# Digit_2.net
KiCad netlist of a schematic drawn in Altium Designer
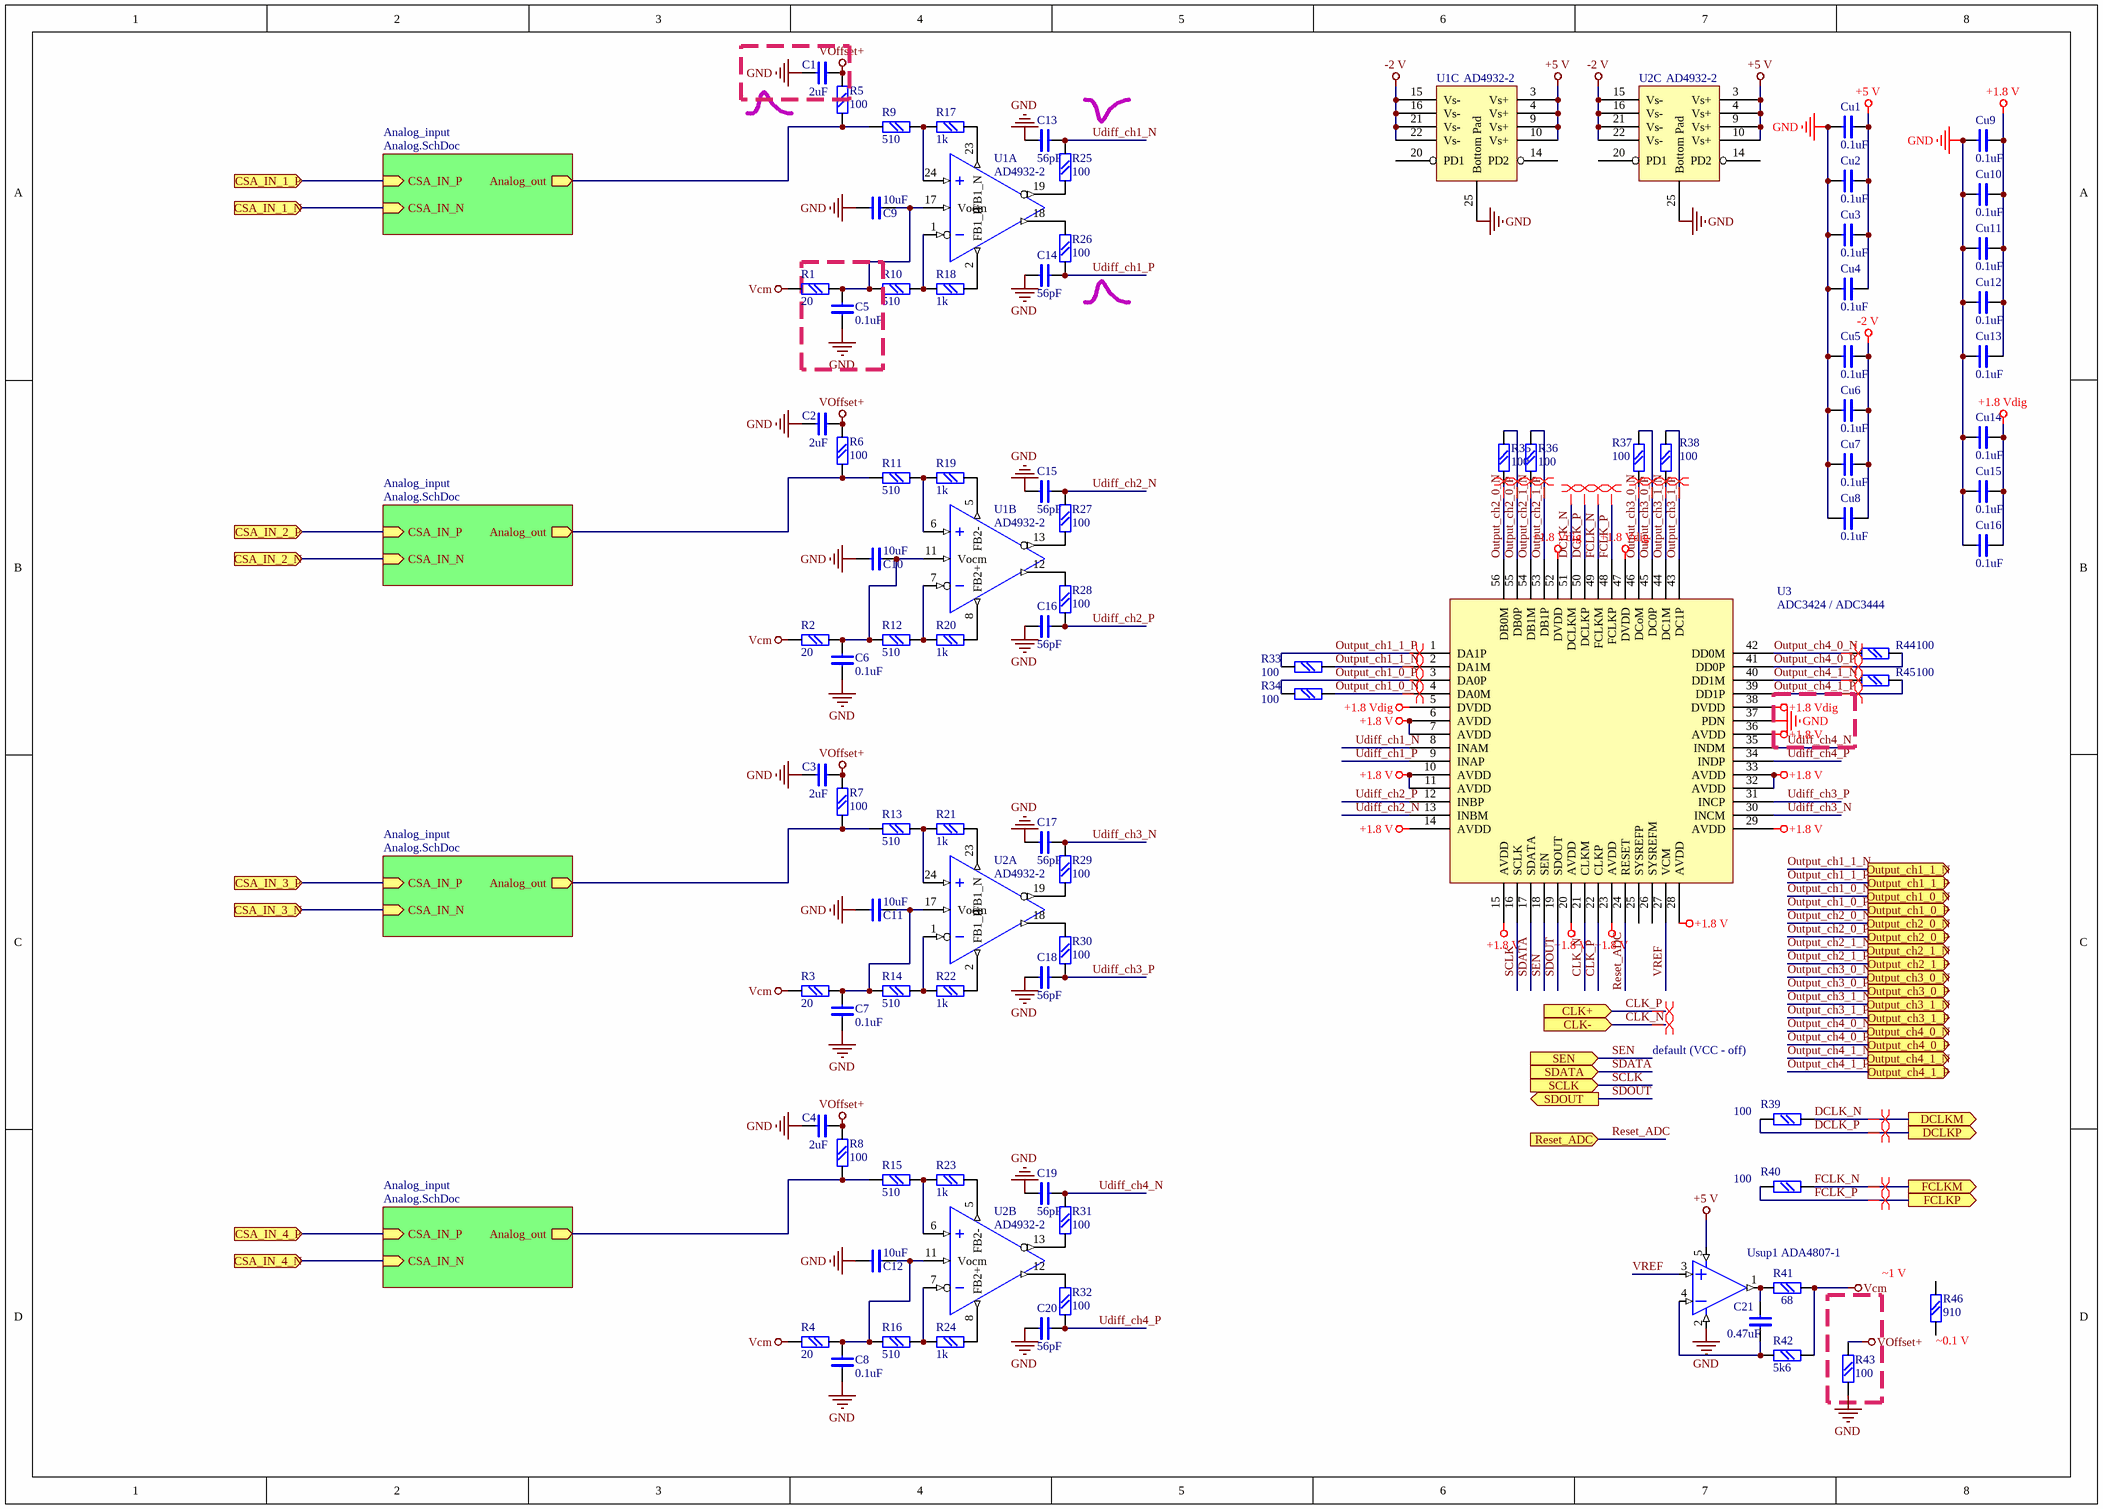
[diagram p0: Digit_2.SchDoc]

(export (version "E")
  (design (tool "Eeschema 10.0.6"))
  (components
    (comp (ref "C1") (value "2uF") (footprint "chip0603") (libsource (lib "vDevice") (part "C")))
    (comp (ref "C2") (value "2uF") (footprint "chip0603") (libsource (lib "vDevice") (part "C")))
    (comp (ref "C3") (value "2uF") (footprint "chip0603") (libsource (lib "vDevice") (part "C")))
    (comp (ref "C4") (value "2uF") (footprint "chip0603") (libsource (lib "vDevice") (part "C")))
    (comp (ref "C5") (value "0.1uF") (footprint "chip0603") (libsource (lib "vDevice") (part "C")))
    (comp (ref "C6") (value "0.1uF") (footprint "chip0603") (libsource (lib "vDevice") (part "C")))
    (comp (ref "C7") (value "0.1uF") (footprint "chip0603") (libsource (lib "vDevice") (part "C")))
    (comp (ref "C8") (value "0.1uF") (footprint "chip0603") (libsource (lib "vDevice") (part "C")))
    (comp (ref "C9") (value "10uF") (footprint "chip0603") (libsource (lib "vDevice") (part "C")))
    (comp (ref "C10") (value "10uF") (footprint "chip0603") (libsource (lib "vDevice") (part "C")))
    (comp (ref "C11") (value "10uF") (footprint "chip0603") (libsource (lib "vDevice") (part "C")))
    (comp (ref "C12") (value "10uF") (footprint "chip0603") (libsource (lib "vDevice") (part "C")))
    (comp (ref "C13") (value "56pF") (footprint "chip0603") (libsource (lib "vDevice") (part "C")))
    (comp (ref "C14") (value "56pF") (footprint "chip0603") (libsource (lib "vDevice") (part "C")))
    (comp (ref "C15") (value "56pF") (footprint "chip0603") (libsource (lib "vDevice") (part "C")))
    (comp (ref "C16") (value "56pF") (footprint "chip0603") (libsource (lib "vDevice") (part "C")))
    (comp (ref "C17") (value "56pF") (footprint "chip0603") (libsource (lib "vDevice") (part "C")))
    (comp (ref "C18") (value "56pF") (footprint "chip0603") (libsource (lib "vDevice") (part "C")))
    (comp (ref "C19") (value "56pF") (footprint "chip0603") (libsource (lib "vDevice") (part "C")))
    (comp (ref "C20") (value "56pF") (footprint "chip0603") (libsource (lib "vDevice") (part "C")))
    (comp (ref "C21") (value "0.47uF") (footprint "chip0603") (libsource (lib "*") (part "C")))
    (comp (ref "Cu1") (value "0.1uF") (footprint "chip0603") (libsource (lib "*") (part "C")))
    (comp (ref "Cu2") (value "0.1uF") (footprint "chip0603") (libsource (lib "*") (part "C")))
    (comp (ref "Cu3") (value "0.1uF") (footprint "chip0603") (libsource (lib "*") (part "C")))
    (comp (ref "Cu4") (value "0.1uF") (footprint "chip0603") (libsource (lib "*") (part "C")))
    (comp (ref "Cu5") (value "0.1uF") (footprint "chip0603") (libsource (lib "*") (part "C")))
    (comp (ref "Cu6") (value "0.1uF") (footprint "chip0603") (libsource (lib "*") (part "C")))
    (comp (ref "Cu7") (value "0.1uF") (footprint "chip0603") (libsource (lib "*") (part "C")))
    (comp (ref "Cu8") (value "0.1uF") (footprint "chip0603") (libsource (lib "*") (part "C")))
    (comp (ref "Cu9") (value "0.1uF") (footprint "chip0603") (libsource (lib "*") (part "C")))
    (comp (ref "Cu10") (value "0.1uF") (footprint "chip0603") (libsource (lib "*") (part "C")))
    (comp (ref "Cu11") (value "0.1uF") (footprint "chip0603") (libsource (lib "*") (part "C")))
    (comp (ref "Cu12") (value "0.1uF") (footprint "chip0603") (libsource (lib "*") (part "C")))
    (comp (ref "Cu13") (value "0.1uF") (footprint "chip0603") (libsource (lib "*") (part "C")))
    (comp (ref "Cu14") (value "0.1uF") (footprint "chip0603") (libsource (lib "*") (part "C")))
    (comp (ref "Cu15") (value "0.1uF") (footprint "chip0603") (libsource (lib "*") (part "C")))
    (comp (ref "Cu16") (value "0.1uF") (footprint "chip0603") (libsource (lib "*") (part "C")))
    (comp (ref "R1") (value "20") (footprint "chip0603") (libsource (lib "vDevice") (part "R")))
    (comp (ref "R2") (value "20") (footprint "chip0603") (libsource (lib "vDevice") (part "R")))
    (comp (ref "R3") (value "20") (footprint "chip0603") (libsource (lib "vDevice") (part "R")))
    (comp (ref "R4") (value "20") (footprint "chip0603") (libsource (lib "vDevice") (part "R")))
    (comp (ref "R5") (value "100") (footprint "chip0603") (libsource (lib "vDevice") (part "R")))
    (comp (ref "R6") (value "100") (footprint "chip0603") (libsource (lib "vDevice") (part "R")))
    (comp (ref "R7") (value "100") (footprint "chip0603") (libsource (lib "vDevice") (part "R")))
    (comp (ref "R8") (value "100") (footprint "chip0603") (libsource (lib "vDevice") (part "R")))
    (comp (ref "R9") (value "510") (footprint "chip0603") (libsource (lib "vDevice") (part "R")))
    (comp (ref "R10") (value "510") (footprint "chip0603") (libsource (lib "vDevice") (part "R")))
    (comp (ref "R11") (value "510") (footprint "chip0603") (libsource (lib "vDevice") (part "R")))
    (comp (ref "R12") (value "510") (footprint "chip0603") (libsource (lib "vDevice") (part "R")))
    (comp (ref "R13") (value "510") (footprint "chip0603") (libsource (lib "vDevice") (part "R")))
    (comp (ref "R14") (value "510") (footprint "chip0603") (libsource (lib "vDevice") (part "R")))
    (comp (ref "R15") (value "510") (footprint "chip0603") (libsource (lib "vDevice") (part "R")))
    (comp (ref "R16") (value "510") (footprint "chip0603") (libsource (lib "vDevice") (part "R")))
    (comp (ref "R17") (value "1k") (footprint "chip0603") (libsource (lib "vDevice") (part "R")))
    (comp (ref "R18") (value "1k") (footprint "chip0603") (libsource (lib "vDevice") (part "R")))
    (comp (ref "R19") (value "1k") (footprint "chip0603") (libsource (lib "vDevice") (part "R")))
    (comp (ref "R20") (value "1k") (footprint "chip0603") (libsource (lib "vDevice") (part "R")))
    (comp (ref "R21") (value "1k") (footprint "chip0603") (libsource (lib "vDevice") (part "R")))
    (comp (ref "R22") (value "1k") (footprint "chip0603") (libsource (lib "vDevice") (part "R")))
    (comp (ref "R23") (value "1k") (footprint "chip0603") (libsource (lib "vDevice") (part "R")))
    (comp (ref "R24") (value "1k") (footprint "chip0603") (libsource (lib "vDevice") (part "R")))
    (comp (ref "R25") (value "100") (footprint "chip0603") (libsource (lib "vDevice") (part "R")))
    (comp (ref "R26") (value "100") (footprint "chip0603") (libsource (lib "vDevice") (part "R")))
    (comp (ref "R27") (value "100") (footprint "chip0603") (libsource (lib "vDevice") (part "R")))
    (comp (ref "R28") (value "100") (footprint "chip0603") (libsource (lib "vDevice") (part "R")))
    (comp (ref "R29") (value "100") (footprint "chip0603") (libsource (lib "vDevice") (part "R")))
    (comp (ref "R30") (value "100") (footprint "chip0603") (libsource (lib "vDevice") (part "R")))
    (comp (ref "R31") (value "100") (footprint "chip0603") (libsource (lib "vDevice") (part "R")))
    (comp (ref "R32") (value "100") (footprint "chip0603") (libsource (lib "vDevice") (part "R")))
    (comp (ref "R33") (value "100") (footprint "0402") (libsource (lib "vDevice") (part "R")))
    (comp (ref "R34") (value "100") (footprint "0402") (libsource (lib "vDevice") (part "R")))
    (comp (ref "R35") (value "100") (footprint "0402") (libsource (lib "vDevice") (part "R")))
    (comp (ref "R36") (value "100") (footprint "0402") (libsource (lib "vDevice") (part "R")))
    (comp (ref "R37") (value "100") (footprint "0402") (libsource (lib "vDevice") (part "R")))
    (comp (ref "R38") (value "100") (footprint "0402") (libsource (lib "vDevice") (part "R")))
    (comp (ref "R39") (value "100") (footprint "0402") (libsource (lib "vDevice") (part "R")))
    (comp (ref "R40") (value "100") (footprint "0402") (libsource (lib "vDevice") (part "R")))
    (comp (ref "R41") (value "68") (footprint "chip0603") (libsource (lib "vDevice") (part "R")))
    (comp (ref "R42") (value "5k6") (footprint "chip0603") (libsource (lib "vDevice") (part "R")))
    (comp (ref "R43") (value "100") (footprint "chip0603") (libsource (lib "vDevice") (part "R")))
    (comp (ref "R44") (value "100") (footprint "0402") (libsource (lib "vDevice") (part "R")))
    (comp (ref "R45") (value "100") (footprint "0402") (libsource (lib "vDevice") (part "R")))
    (comp (ref "R46") (value "910") (footprint "chip0603") (libsource (lib "vDevice") (part "R")))
    (comp (ref "U1")
      (value "AD4932-2")
      (footprint "CP-24-13")
      (libsource (lib "Backup of Mylib") (part "AD4932-2"))
    )
    (comp (ref "U2") (value "AD4932-2") (footprint "CP-24-13") (libsource (lib "") (part "AD4932-2_1")))
    (comp (ref "U3")
      (value "ADC3424 / ADC3444")
      (footprint "PQFN-56")
      (libsource (lib "Backup of Mylib") (part "ADC3424"))
    )
    (comp (ref "Usup1")
      (value "ADA4807-1")
      (footprint "SOT23-5")
      (libsource (lib "vAnalog") (part "AD8005ART"))
    )
  )
  (nets
    (net (code "1") (name "+1.8 V") (class "Default")
      (node (ref "Cu10") (pin "2") (pinfunction "2_2") (pintype "passive"))
      (node (ref "Cu11") (pin "2") (pinfunction "2_2") (pintype "passive"))
      (node (ref "Cu12") (pin "2") (pinfunction "2_2") (pintype "passive"))
      (node (ref "Cu13") (pin "2") (pinfunction "2_2") (pintype "passive"))
      (node (ref "Cu9") (pin "2") (pinfunction "2_2") (pintype "passive"))
      (node (ref "U3") (pin "10") (pinfunction "AVDD_10") (pintype "passive"))
      (node (ref "U3") (pin "11") (pinfunction "AVDD_11") (pintype "passive"))
      (node (ref "U3") (pin "14") (pinfunction "AVDD_14") (pintype "passive"))
      (node (ref "U3") (pin "15") (pinfunction "AVDD_15") (pintype "passive"))
      (node (ref "U3") (pin "20") (pinfunction "AVDD_20") (pintype "passive"))
      (node (ref "U3") (pin "23") (pinfunction "AVDD_23") (pintype "passive"))
      (node (ref "U3") (pin "28") (pinfunction "AVDD_28") (pintype "passive"))
      (node (ref "U3") (pin "29") (pinfunction "AVDD_29") (pintype "passive"))
      (node (ref "U3") (pin "32") (pinfunction "AVDD_32") (pintype "passive"))
      (node (ref "U3") (pin "33") (pinfunction "AVDD_33") (pintype "passive"))
      (node (ref "U3") (pin "36") (pinfunction "AVDD_36") (pintype "passive"))
      (node (ref "U3") (pin "6") (pinfunction "AVDD_6") (pintype "passive"))
      (node (ref "U3") (pin "7") (pinfunction "AVDD_7") (pintype "passive"))
    )
    (net (code "2") (name "+1.8 Vdig") (class "Default")
      (node (ref "Cu14") (pin "2") (pinfunction "2_2") (pintype "passive"))
      (node (ref "Cu15") (pin "2") (pinfunction "2_2") (pintype "passive"))
      (node (ref "Cu16") (pin "2") (pinfunction "2_2") (pintype "passive"))
      (node (ref "U3") (pin "38") (pinfunction "DVDD_38") (pintype "passive"))
      (node (ref "U3") (pin "47") (pinfunction "DVDD_47") (pintype "passive"))
      (node (ref "U3") (pin "5") (pinfunction "DVDD_5") (pintype "passive"))
      (node (ref "U3") (pin "52") (pinfunction "DVDD_52") (pintype "passive"))
    )
    (net (code "3") (name "+5 V") (class "Default")
      (node (ref "Cu1") (pin "2") (pinfunction "2_2") (pintype "passive"))
      (node (ref "Cu2") (pin "2") (pinfunction "2_2") (pintype "passive"))
      (node (ref "Cu3") (pin "2") (pinfunction "2_2") (pintype "passive"))
      (node (ref "Cu4") (pin "2") (pinfunction "2_2") (pintype "passive"))
      (node (ref "U1") (pin "10") (pinfunction "Vs+_10") (pintype "power_in"))
      (node (ref "U1") (pin "3") (pinfunction "Vs+_3") (pintype "power_in"))
      (node (ref "U1") (pin "4") (pinfunction "Vs+_4") (pintype "power_in"))
      (node (ref "U1") (pin "9") (pinfunction "Vs+_9") (pintype "power_in"))
      (node (ref "U2") (pin "10") (pinfunction "Vs+_10") (pintype "power_in"))
      (node (ref "U2") (pin "3") (pinfunction "Vs+_3") (pintype "power_in"))
      (node (ref "U2") (pin "4") (pinfunction "Vs+_4") (pintype "power_in"))
      (node (ref "U2") (pin "9") (pinfunction "Vs+_9") (pintype "power_in"))
      (node (ref "Usup1") (pin "5") (pinfunction "E+_5") (pintype "input"))
    )
    (net (code "4") (name "-2 V") (class "Default")
      (node (ref "Cu5") (pin "2") (pinfunction "2_2") (pintype "passive"))
      (node (ref "Cu6") (pin "2") (pinfunction "2_2") (pintype "passive"))
      (node (ref "Cu7") (pin "2") (pinfunction "2_2") (pintype "passive"))
      (node (ref "Cu8") (pin "2") (pinfunction "2_2") (pintype "passive"))
      (node (ref "U1") (pin "15") (pinfunction "Vs-_15") (pintype "power_in"))
      (node (ref "U1") (pin "16") (pinfunction "Vs-_16") (pintype "power_in"))
      (node (ref "U1") (pin "21") (pinfunction "Vs-_21") (pintype "power_in"))
      (node (ref "U1") (pin "22") (pinfunction "Vs-_22") (pintype "power_in"))
      (node (ref "U2") (pin "15") (pinfunction "Vs-_15") (pintype "power_in"))
      (node (ref "U2") (pin "16") (pinfunction "Vs-_16") (pintype "power_in"))
      (node (ref "U2") (pin "21") (pinfunction "Vs-_21") (pintype "power_in"))
      (node (ref "U2") (pin "22") (pinfunction "Vs-_22") (pintype "power_in"))
    )
    (net (code "5") (name "/Analog_out") (class "Default")
      (node (ref "R15") (pin "2") (pinfunction "2_2") (pintype "passive"))
      (node (ref "R8") (pin "1") (pinfunction "1_1") (pintype "passive"))
    )
    (net (code "6") (name "/Analog_out_1") (class "Default")
      (node (ref "R11") (pin "2") (pinfunction "2_2") (pintype "passive"))
      (node (ref "R6") (pin "1") (pinfunction "1_1") (pintype "passive"))
    )
    (net (code "7") (name "/Analog_out_2") (class "Default")
      (node (ref "R5") (pin "1") (pinfunction "1_1") (pintype "passive"))
      (node (ref "R9") (pin "2") (pinfunction "2_2") (pintype "passive"))
    )
    (net (code "8") (name "/Analog_out_3") (class "Default")
      (node (ref "R13") (pin "2") (pinfunction "2_2") (pintype "passive"))
      (node (ref "R7") (pin "1") (pinfunction "1_1") (pintype "passive"))
    )
    (net (code "9") (name "/CLK_N") (class "Default")
      (node (ref "U3") (pin "21") (pinfunction "CLKM_21") (pintype "passive"))
    )
    (net (code "10") (name "/CLK_P") (class "Default")
      (node (ref "U3") (pin "22") (pinfunction "CLKP_22") (pintype "passive"))
    )
    (net (code "19") (name "/DCLK_N") (class "Default")
      (node (ref "R39") (pin "2") (pinfunction "2_2") (pintype "passive"))
      (node (ref "U3") (pin "51") (pinfunction "DCLKM_51") (pintype "passive"))
    )
    (net (code "20") (name "/DCLK_P") (class "Default")
      (node (ref "R39") (pin "1") (pinfunction "1_1") (pintype "passive"))
      (node (ref "U3") (pin "50") (pinfunction "DCLKP_50") (pintype "passive"))
    )
    (net (code "21") (name "/FCLK_N") (class "Default")
      (node (ref "R40") (pin "2") (pinfunction "2_2") (pintype "passive"))
      (node (ref "U3") (pin "49") (pinfunction "FCLKM_49") (pintype "passive"))
    )
    (net (code "22") (name "/FCLK_P") (class "Default")
      (node (ref "R40") (pin "1") (pinfunction "1_1") (pintype "passive"))
      (node (ref "U3") (pin "48") (pinfunction "FCLKP_48") (pintype "passive"))
    )
    (net (code "23") (name "/Output_ch1_0_N") (class "Default")
      (node (ref "R34") (pin "2") (pinfunction "2_2") (pintype "passive"))
      (node (ref "U3") (pin "4") (pinfunction "DA0M_4") (pintype "passive"))
    )
    (net (code "24") (name "/Output_ch1_0_P") (class "Default")
      (node (ref "R34") (pin "1") (pinfunction "1_1") (pintype "passive"))
      (node (ref "U3") (pin "3") (pinfunction "DA0P_3") (pintype "passive"))
    )
    (net (code "25") (name "/Output_ch1_1_N") (class "Default")
      (node (ref "R33") (pin "2") (pinfunction "2_2") (pintype "passive"))
      (node (ref "U3") (pin "2") (pinfunction "DA1M_2") (pintype "passive"))
    )
    (net (code "26") (name "/Output_ch1_1_P") (class "Default")
      (node (ref "R33") (pin "1") (pinfunction "1_1") (pintype "passive"))
      (node (ref "U3") (pin "1") (pinfunction "DA1P_1") (pintype "passive"))
    )
    (net (code "27") (name "/Output_ch2_0_N") (class "Default")
      (node (ref "R35") (pin "1") (pinfunction "1_1") (pintype "passive"))
      (node (ref "U3") (pin "56") (pinfunction "DB0M_56") (pintype "passive"))
    )
    (net (code "28") (name "/Output_ch2_0_P") (class "Default")
      (node (ref "R35") (pin "2") (pinfunction "2_2") (pintype "passive"))
      (node (ref "U3") (pin "55") (pinfunction "DB0P_55") (pintype "passive"))
    )
    (net (code "29") (name "/Output_ch2_1_N") (class "Default")
      (node (ref "R36") (pin "1") (pinfunction "1_1") (pintype "passive"))
      (node (ref "U3") (pin "54") (pinfunction "DB1M_54") (pintype "passive"))
    )
    (net (code "30") (name "/Output_ch2_1_P") (class "Default")
      (node (ref "R36") (pin "2") (pinfunction "2_2") (pintype "passive"))
      (node (ref "U3") (pin "53") (pinfunction "DB1P_53") (pintype "passive"))
    )
    (net (code "31") (name "/Output_ch3_0_N") (class "Default")
      (node (ref "R37") (pin "1") (pinfunction "1_1") (pintype "passive"))
      (node (ref "U3") (pin "46") (pinfunction "DCoM_46") (pintype "passive"))
    )
    (net (code "32") (name "/Output_ch3_0_P") (class "Default")
      (node (ref "R37") (pin "2") (pinfunction "2_2") (pintype "passive"))
      (node (ref "U3") (pin "45") (pinfunction "DC0P_45") (pintype "passive"))
    )
    (net (code "33") (name "/Output_ch3_1_N") (class "Default")
      (node (ref "R38") (pin "1") (pinfunction "1_1") (pintype "passive"))
      (node (ref "U3") (pin "44") (pinfunction "DC1M_44") (pintype "passive"))
    )
    (net (code "34") (name "/Output_ch3_1_P") (class "Default")
      (node (ref "R38") (pin "2") (pinfunction "2_2") (pintype "passive"))
      (node (ref "U3") (pin "43") (pinfunction "DC1P_43") (pintype "passive"))
    )
    (net (code "35") (name "/Output_ch4_0_N") (class "Default")
      (node (ref "R44") (pin "1") (pinfunction "1_1") (pintype "passive"))
      (node (ref "U3") (pin "42") (pinfunction "DD0M_42") (pintype "passive"))
    )
    (net (code "36") (name "/Output_ch4_0_P") (class "Default")
      (node (ref "R44") (pin "2") (pinfunction "2_2") (pintype "passive"))
      (node (ref "U3") (pin "41") (pinfunction "DD0P_41") (pintype "passive"))
    )
    (net (code "37") (name "/Output_ch4_1_N") (class "Default")
      (node (ref "R45") (pin "1") (pinfunction "1_1") (pintype "passive"))
      (node (ref "U3") (pin "40") (pinfunction "DD1M_40") (pintype "passive"))
    )
    (net (code "38") (name "/Output_ch4_1_P") (class "Default")
      (node (ref "R45") (pin "2") (pinfunction "2_2") (pintype "passive"))
      (node (ref "U3") (pin "39") (pinfunction "DD1P_39") (pintype "passive"))
    )
    (net (code "39") (name "/Reset_ADC") (class "Default")
      (node (ref "U3") (pin "24") (pinfunction "RESET_24") (pintype "passive"))
    )
    (net (code "40") (name "/SCLK") (class "Default")
      (node (ref "U3") (pin "16") (pinfunction "SCLK_16") (pintype "passive"))
    )
    (net (code "41") (name "/SDATA") (class "Default")
      (node (ref "U3") (pin "17") (pinfunction "SDATA_17") (pintype "passive"))
    )
    (net (code "42") (name "/SDOUT") (class "Default")
      (node (ref "U3") (pin "19") (pinfunction "SDOUT_19") (pintype "passive"))
    )
    (net (code "43") (name "/SEN") (class "Default")
      (node (ref "U3") (pin "18") (pinfunction "SEN_18") (pintype "passive"))
    )
    (net (code "44") (name "/Udiff_ch1_N") (class "Default")
      (node (ref "C13") (pin "1") (pinfunction "1_1") (pintype "passive"))
      (node (ref "R25") (pin "2") (pinfunction "2_2") (pintype "passive"))
      (node (ref "U3") (pin "8") (pinfunction "INAM_8") (pintype "passive"))
    )
    (net (code "45") (name "/Udiff_ch1_P") (class "Default")
      (node (ref "C14") (pin "2") (pinfunction "2_2") (pintype "passive"))
      (node (ref "R26") (pin "2") (pinfunction "2_2") (pintype "passive"))
      (node (ref "U3") (pin "9") (pinfunction "INAP_9") (pintype "passive"))
    )
    (net (code "46") (name "/Udiff_ch2_N") (class "Default")
      (node (ref "C15") (pin "1") (pinfunction "1_1") (pintype "passive"))
      (node (ref "R27") (pin "2") (pinfunction "2_2") (pintype "passive"))
      (node (ref "U3") (pin "13") (pinfunction "INBM_13") (pintype "passive"))
    )
    (net (code "47") (name "/Udiff_ch2_P") (class "Default")
      (node (ref "C16") (pin "2") (pinfunction "2_2") (pintype "passive"))
      (node (ref "R28") (pin "2") (pinfunction "2_2") (pintype "passive"))
      (node (ref "U3") (pin "12") (pinfunction "INBP_12") (pintype "passive"))
    )
    (net (code "48") (name "/Udiff_ch3_N") (class "Default")
      (node (ref "C17") (pin "1") (pinfunction "1_1") (pintype "passive"))
      (node (ref "R29") (pin "2") (pinfunction "2_2") (pintype "passive"))
      (node (ref "U3") (pin "30") (pinfunction "INCM_30") (pintype "passive"))
    )
    (net (code "49") (name "/Udiff_ch3_P") (class "Default")
      (node (ref "C18") (pin "2") (pinfunction "2_2") (pintype "passive"))
      (node (ref "R30") (pin "2") (pinfunction "2_2") (pintype "passive"))
      (node (ref "U3") (pin "31") (pinfunction "INCP_31") (pintype "passive"))
    )
    (net (code "50") (name "/Udiff_ch4_N") (class "Default")
      (node (ref "C19") (pin "1") (pinfunction "1_1") (pintype "passive"))
      (node (ref "R31") (pin "2") (pinfunction "2_2") (pintype "passive"))
      (node (ref "U3") (pin "35") (pinfunction "INDM_35") (pintype "passive"))
    )
    (net (code "51") (name "/Udiff_ch4_P") (class "Default")
      (node (ref "C20") (pin "2") (pinfunction "2_2") (pintype "passive"))
      (node (ref "R32") (pin "2") (pinfunction "2_2") (pintype "passive"))
      (node (ref "U3") (pin "34") (pinfunction "INDP_34") (pintype "passive"))
    )
    (net (code "52") (name "/VREF") (class "Default")
      (node (ref "U3") (pin "27") (pinfunction "VCM_27") (pintype "passive"))
      (node (ref "Usup1") (pin "3") (pinfunction "+IN_3") (pintype "input"))
    )
    (net (code "53") (name "GND") (class "Default")
      (node (ref "C1") (pin "1") (pinfunction "1_1") (pintype "passive"))
      (node (ref "C10") (pin "1") (pinfunction "1_1") (pintype "passive"))
      (node (ref "C11") (pin "1") (pinfunction "1_1") (pintype "passive"))
      (node (ref "C12") (pin "1") (pinfunction "1_1") (pintype "passive"))
      (node (ref "C13") (pin "2") (pinfunction "2_2") (pintype "passive"))
      (node (ref "C14") (pin "1") (pinfunction "1_1") (pintype "passive"))
      (node (ref "C15") (pin "2") (pinfunction "2_2") (pintype "passive"))
      (node (ref "C16") (pin "1") (pinfunction "1_1") (pintype "passive"))
      (node (ref "C17") (pin "2") (pinfunction "2_2") (pintype "passive"))
      (node (ref "C18") (pin "1") (pinfunction "1_1") (pintype "passive"))
      (node (ref "C19") (pin "2") (pinfunction "2_2") (pintype "passive"))
      (node (ref "C2") (pin "1") (pinfunction "1_1") (pintype "passive"))
      (node (ref "C20") (pin "1") (pinfunction "1_1") (pintype "passive"))
      (node (ref "C3") (pin "1") (pinfunction "1_1") (pintype "passive"))
      (node (ref "C4") (pin "1") (pinfunction "1_1") (pintype "passive"))
      (node (ref "C5") (pin "1") (pinfunction "1_1") (pintype "passive"))
      (node (ref "C6") (pin "1") (pinfunction "1_1") (pintype "passive"))
      (node (ref "C7") (pin "1") (pinfunction "1_1") (pintype "passive"))
      (node (ref "C8") (pin "1") (pinfunction "1_1") (pintype "passive"))
      (node (ref "C9") (pin "1") (pinfunction "1_1") (pintype "passive"))
      (node (ref "Cu1") (pin "1") (pinfunction "1_1") (pintype "passive"))
      (node (ref "Cu10") (pin "1") (pinfunction "1_1") (pintype "passive"))
      (node (ref "Cu11") (pin "1") (pinfunction "1_1") (pintype "passive"))
      (node (ref "Cu12") (pin "1") (pinfunction "1_1") (pintype "passive"))
      (node (ref "Cu13") (pin "1") (pinfunction "1_1") (pintype "passive"))
      (node (ref "Cu14") (pin "1") (pinfunction "1_1") (pintype "passive"))
      (node (ref "Cu15") (pin "1") (pinfunction "1_1") (pintype "passive"))
      (node (ref "Cu16") (pin "1") (pinfunction "1_1") (pintype "passive"))
      (node (ref "Cu2") (pin "1") (pinfunction "1_1") (pintype "passive"))
      (node (ref "Cu3") (pin "1") (pinfunction "1_1") (pintype "passive"))
      (node (ref "Cu4") (pin "1") (pinfunction "1_1") (pintype "passive"))
      (node (ref "Cu5") (pin "1") (pinfunction "1_1") (pintype "passive"))
      (node (ref "Cu6") (pin "1") (pinfunction "1_1") (pintype "passive"))
      (node (ref "Cu7") (pin "1") (pinfunction "1_1") (pintype "passive"))
      (node (ref "Cu8") (pin "1") (pinfunction "1_1") (pintype "passive"))
      (node (ref "Cu9") (pin "1") (pinfunction "1_1") (pintype "passive"))
      (node (ref "R43") (pin "2") (pinfunction "2_2") (pintype "passive"))
      (node (ref "U1") (pin "25") (pinfunction "Bottom_Pad_25") (pintype "passive"))
      (node (ref "U2") (pin "25") (pinfunction "Bottom_Pad_25") (pintype "passive"))
      (node (ref "U3") (pin "37") (pinfunction "PDN_37") (pintype "passive"))
      (node (ref "Usup1") (pin "2") (pinfunction "E-_2") (pintype "input"))
    )
    (net (code "54") (name "Net-(U1A-FB1+)") (class "Default")
      (node (ref "R18") (pin "1") (pinfunction "1_1") (pintype "passive"))
      (node (ref "U1") (pin "2") (pinfunction "FB1+_2") (pintype "output"))
    )
    (net (code "55") (name "Net-(U1A-FB1-)") (class "Default")
      (node (ref "R17") (pin "2") (pinfunction "2_2") (pintype "passive"))
      (node (ref "U1") (pin "23") (pinfunction "FB1-_23") (pintype "output"))
    )
    (net (code "56") (name "Net-(U1A-In+)") (class "Default")
      (node (ref "R17") (pin "1") (pinfunction "1_1") (pintype "passive"))
      (node (ref "R9") (pin "1") (pinfunction "1_1") (pintype "passive"))
      (node (ref "U1") (pin "24") (pinfunction "In+_24") (pintype "input"))
    )
    (net (code "57") (name "Net-(U1A-In-)") (class "Default")
      (node (ref "R10") (pin "1") (pinfunction "1_1") (pintype "passive"))
      (node (ref "R18") (pin "2") (pinfunction "2_2") (pintype "passive"))
      (node (ref "U1") (pin "1") (pinfunction "In-_1") (pintype "input"))
    )
    (net (code "58") (name "Net-(U1A-Out+)") (class "Default")
      (node (ref "R26") (pin "1") (pinfunction "1_1") (pintype "passive"))
      (node (ref "U1") (pin "18") (pinfunction "Out+_18") (pintype "output"))
    )
    (net (code "59") (name "Net-(U1A-Out-)") (class "Default")
      (node (ref "R25") (pin "1") (pinfunction "1_1") (pintype "passive"))
      (node (ref "U1") (pin "19") (pinfunction "Out-_19") (pintype "output"))
    )
    (net (code "60") (name "Net-(U1A-Vocm)") (class "Default")
      (node (ref "C5") (pin "2") (pinfunction "2_2") (pintype "passive"))
      (node (ref "C9") (pin "2") (pinfunction "2_2") (pintype "passive"))
      (node (ref "R1") (pin "1") (pinfunction "1_1") (pintype "passive"))
      (node (ref "R10") (pin "2") (pinfunction "2_2") (pintype "passive"))
      (node (ref "U1") (pin "17") (pinfunction "Vocm_17") (pintype "input"))
    )
    (net (code "61") (name "Net-(U1B-FB2+)") (class "Default")
      (node (ref "R20") (pin "1") (pinfunction "1_1") (pintype "passive"))
      (node (ref "U1") (pin "8") (pinfunction "FB2+_8") (pintype "output"))
    )
    (net (code "62") (name "Net-(U1B-FB2-)") (class "Default")
      (node (ref "R19") (pin "2") (pinfunction "2_2") (pintype "passive"))
      (node (ref "U1") (pin "5") (pinfunction "FB2-_5") (pintype "output"))
    )
    (net (code "63") (name "Net-(U1B-In+)") (class "Default")
      (node (ref "R11") (pin "1") (pinfunction "1_1") (pintype "passive"))
      (node (ref "R19") (pin "1") (pinfunction "1_1") (pintype "passive"))
      (node (ref "U1") (pin "6") (pinfunction "In+_6") (pintype "input"))
    )
    (net (code "64") (name "Net-(U1B-In-)") (class "Default")
      (node (ref "R12") (pin "1") (pinfunction "1_1") (pintype "passive"))
      (node (ref "R20") (pin "2") (pinfunction "2_2") (pintype "passive"))
      (node (ref "U1") (pin "7") (pinfunction "In-_7") (pintype "input"))
    )
    (net (code "65") (name "Net-(U1B-Out+)") (class "Default")
      (node (ref "R28") (pin "1") (pinfunction "1_1") (pintype "passive"))
      (node (ref "U1") (pin "12") (pinfunction "Out+_12") (pintype "output"))
    )
    (net (code "66") (name "Net-(U1B-Out-)") (class "Default")
      (node (ref "R27") (pin "1") (pinfunction "1_1") (pintype "passive"))
      (node (ref "U1") (pin "13") (pinfunction "Out-_13") (pintype "output"))
    )
    (net (code "67") (name "Net-(U1B-Vocm)") (class "Default")
      (node (ref "C10") (pin "2") (pinfunction "2_2") (pintype "passive"))
      (node (ref "C6") (pin "2") (pinfunction "2_2") (pintype "passive"))
      (node (ref "R12") (pin "2") (pinfunction "2_2") (pintype "passive"))
      (node (ref "R2") (pin "1") (pinfunction "1_1") (pintype "passive"))
      (node (ref "U1") (pin "11") (pinfunction "Vocm_11") (pintype "input"))
    )
    (net (code "68") (name "Net-(U2A-FB1+)") (class "Default")
      (node (ref "R22") (pin "1") (pinfunction "1_1") (pintype "passive"))
      (node (ref "U2") (pin "2") (pinfunction "FB1+_2") (pintype "output"))
    )
    (net (code "69") (name "Net-(U2A-FB1-)") (class "Default")
      (node (ref "R21") (pin "2") (pinfunction "2_2") (pintype "passive"))
      (node (ref "U2") (pin "23") (pinfunction "FB1-_23") (pintype "output"))
    )
    (net (code "70") (name "Net-(U2A-In+)") (class "Default")
      (node (ref "R13") (pin "1") (pinfunction "1_1") (pintype "passive"))
      (node (ref "R21") (pin "1") (pinfunction "1_1") (pintype "passive"))
      (node (ref "U2") (pin "24") (pinfunction "In+_24") (pintype "input"))
    )
    (net (code "71") (name "Net-(U2A-In-)") (class "Default")
      (node (ref "R14") (pin "1") (pinfunction "1_1") (pintype "passive"))
      (node (ref "R22") (pin "2") (pinfunction "2_2") (pintype "passive"))
      (node (ref "U2") (pin "1") (pinfunction "In-_1") (pintype "input"))
    )
    (net (code "72") (name "Net-(U2A-Out+)") (class "Default")
      (node (ref "R30") (pin "1") (pinfunction "1_1") (pintype "passive"))
      (node (ref "U2") (pin "18") (pinfunction "Out+_18") (pintype "output"))
    )
    (net (code "73") (name "Net-(U2A-Out-)") (class "Default")
      (node (ref "R29") (pin "1") (pinfunction "1_1") (pintype "passive"))
      (node (ref "U2") (pin "19") (pinfunction "Out-_19") (pintype "output"))
    )
    (net (code "74") (name "Net-(U2A-Vocm)") (class "Default")
      (node (ref "C11") (pin "2") (pinfunction "2_2") (pintype "passive"))
      (node (ref "C7") (pin "2") (pinfunction "2_2") (pintype "passive"))
      (node (ref "R14") (pin "2") (pinfunction "2_2") (pintype "passive"))
      (node (ref "R3") (pin "1") (pinfunction "1_1") (pintype "passive"))
      (node (ref "U2") (pin "17") (pinfunction "Vocm_17") (pintype "input"))
    )
    (net (code "75") (name "Net-(U2B-FB2+)") (class "Default")
      (node (ref "R24") (pin "1") (pinfunction "1_1") (pintype "passive"))
      (node (ref "U2") (pin "8") (pinfunction "FB2+_8") (pintype "output"))
    )
    (net (code "76") (name "Net-(U2B-FB2-)") (class "Default")
      (node (ref "R23") (pin "2") (pinfunction "2_2") (pintype "passive"))
      (node (ref "U2") (pin "5") (pinfunction "FB2-_5") (pintype "output"))
    )
    (net (code "77") (name "Net-(U2B-In+)") (class "Default")
      (node (ref "R15") (pin "1") (pinfunction "1_1") (pintype "passive"))
      (node (ref "R23") (pin "1") (pinfunction "1_1") (pintype "passive"))
      (node (ref "U2") (pin "6") (pinfunction "In+_6") (pintype "input"))
    )
    (net (code "78") (name "Net-(U2B-In-)") (class "Default")
      (node (ref "R16") (pin "1") (pinfunction "1_1") (pintype "passive"))
      (node (ref "R24") (pin "2") (pinfunction "2_2") (pintype "passive"))
      (node (ref "U2") (pin "7") (pinfunction "In-_7") (pintype "input"))
    )
    (net (code "79") (name "Net-(U2B-Out+)") (class "Default")
      (node (ref "R32") (pin "1") (pinfunction "1_1") (pintype "passive"))
      (node (ref "U2") (pin "12") (pinfunction "Out+_12") (pintype "output"))
    )
    (net (code "80") (name "Net-(U2B-Out-)") (class "Default")
      (node (ref "R31") (pin "1") (pinfunction "1_1") (pintype "passive"))
      (node (ref "U2") (pin "13") (pinfunction "Out-_13") (pintype "output"))
    )
    (net (code "81") (name "Net-(U2B-Vocm)") (class "Default")
      (node (ref "C12") (pin "2") (pinfunction "2_2") (pintype "passive"))
      (node (ref "C8") (pin "2") (pinfunction "2_2") (pintype "passive"))
      (node (ref "R16") (pin "2") (pinfunction "2_2") (pintype "passive"))
      (node (ref "R4") (pin "1") (pinfunction "1_1") (pintype "passive"))
      (node (ref "U2") (pin "11") (pinfunction "Vocm_11") (pintype "input"))
    )
    (net (code "82") (name "Net-(Usup1--IN)") (class "Default")
      (node (ref "C21") (pin "2") (pinfunction "2_2") (pintype "passive"))
      (node (ref "R42") (pin "1") (pinfunction "1_1") (pintype "passive"))
      (node (ref "Usup1") (pin "4") (pinfunction "-IN_4") (pintype "input"))
    )
    (net (code "83") (name "Net-(Usup1-OUT)") (class "Default")
      (node (ref "C21") (pin "1") (pinfunction "1_1") (pintype "passive"))
      (node (ref "R41") (pin "1") (pinfunction "1_1") (pintype "passive"))
      (node (ref "Usup1") (pin "1") (pinfunction "OUT_1") (pintype "output"))
    )
    (net (code "84") (name "VOffset+") (class "Default")
      (node (ref "C1") (pin "2") (pinfunction "2_2") (pintype "passive"))
      (node (ref "C2") (pin "2") (pinfunction "2_2") (pintype "passive"))
      (node (ref "C3") (pin "2") (pinfunction "2_2") (pintype "passive"))
      (node (ref "C4") (pin "2") (pinfunction "2_2") (pintype "passive"))
      (node (ref "R43") (pin "1") (pinfunction "1_1") (pintype "passive"))
      (node (ref "R5") (pin "2") (pinfunction "2_2") (pintype "passive"))
      (node (ref "R6") (pin "2") (pinfunction "2_2") (pintype "passive"))
      (node (ref "R7") (pin "2") (pinfunction "2_2") (pintype "passive"))
      (node (ref "R8") (pin "2") (pinfunction "2_2") (pintype "passive"))
    )
    (net (code "85") (name "Vcm") (class "Default")
      (node (ref "R1") (pin "2") (pinfunction "2_2") (pintype "passive"))
      (node (ref "R2") (pin "2") (pinfunction "2_2") (pintype "passive"))
      (node (ref "R3") (pin "2") (pinfunction "2_2") (pintype "passive"))
      (node (ref "R4") (pin "2") (pinfunction "2_2") (pintype "passive"))
      (node (ref "R41") (pin "2") (pinfunction "2_2") (pintype "passive"))
      (node (ref "R42") (pin "2") (pinfunction "2_2") (pintype "passive"))
    )
    (net (code "86") (name "unconnected-(R46-Pad1)") (class "Default")
      (node (ref "R46") (pin "1") (pinfunction "1_1") (pintype "passive"))
    )
    (net (code "87") (name "unconnected-(R46-Pad2)") (class "Default")
      (node (ref "R46") (pin "2") (pinfunction "2_2") (pintype "passive"))
    )
    (net (code "88") (name "unconnected-(U1C-PD1-Pad20)") (class "Default")
      (node (ref "U1") (pin "20") (pinfunction "PD1_20") (pintype "passive"))
    )
    (net (code "89") (name "unconnected-(U1C-PD2-Pad14)") (class "Default")
      (node (ref "U1") (pin "14") (pinfunction "PD2_14") (pintype "passive"))
    )
    (net (code "90") (name "unconnected-(U2C-PD1-Pad20)") (class "Default")
      (node (ref "U2") (pin "20") (pinfunction "PD1_20") (pintype "passive"))
    )
    (net (code "91") (name "unconnected-(U2C-PD2-Pad14)") (class "Default")
      (node (ref "U2") (pin "14") (pinfunction "PD2_14") (pintype "passive"))
    )
    (net (code "92") (name "unconnected-(U3-SYSREFM-Pad26)") (class "Default")
      (node (ref "U3") (pin "26") (pinfunction "SYSREFM_26") (pintype "passive"))
    )
    (net (code "93") (name "unconnected-(U3-SYSREFP-Pad25)") (class "Default")
      (node (ref "U3") (pin "25") (pinfunction "SYSREFP_25") (pintype "passive"))
    )
  )
)
